# gyro-board.net
KiCad netlist of a schematic drawn in EAGLE
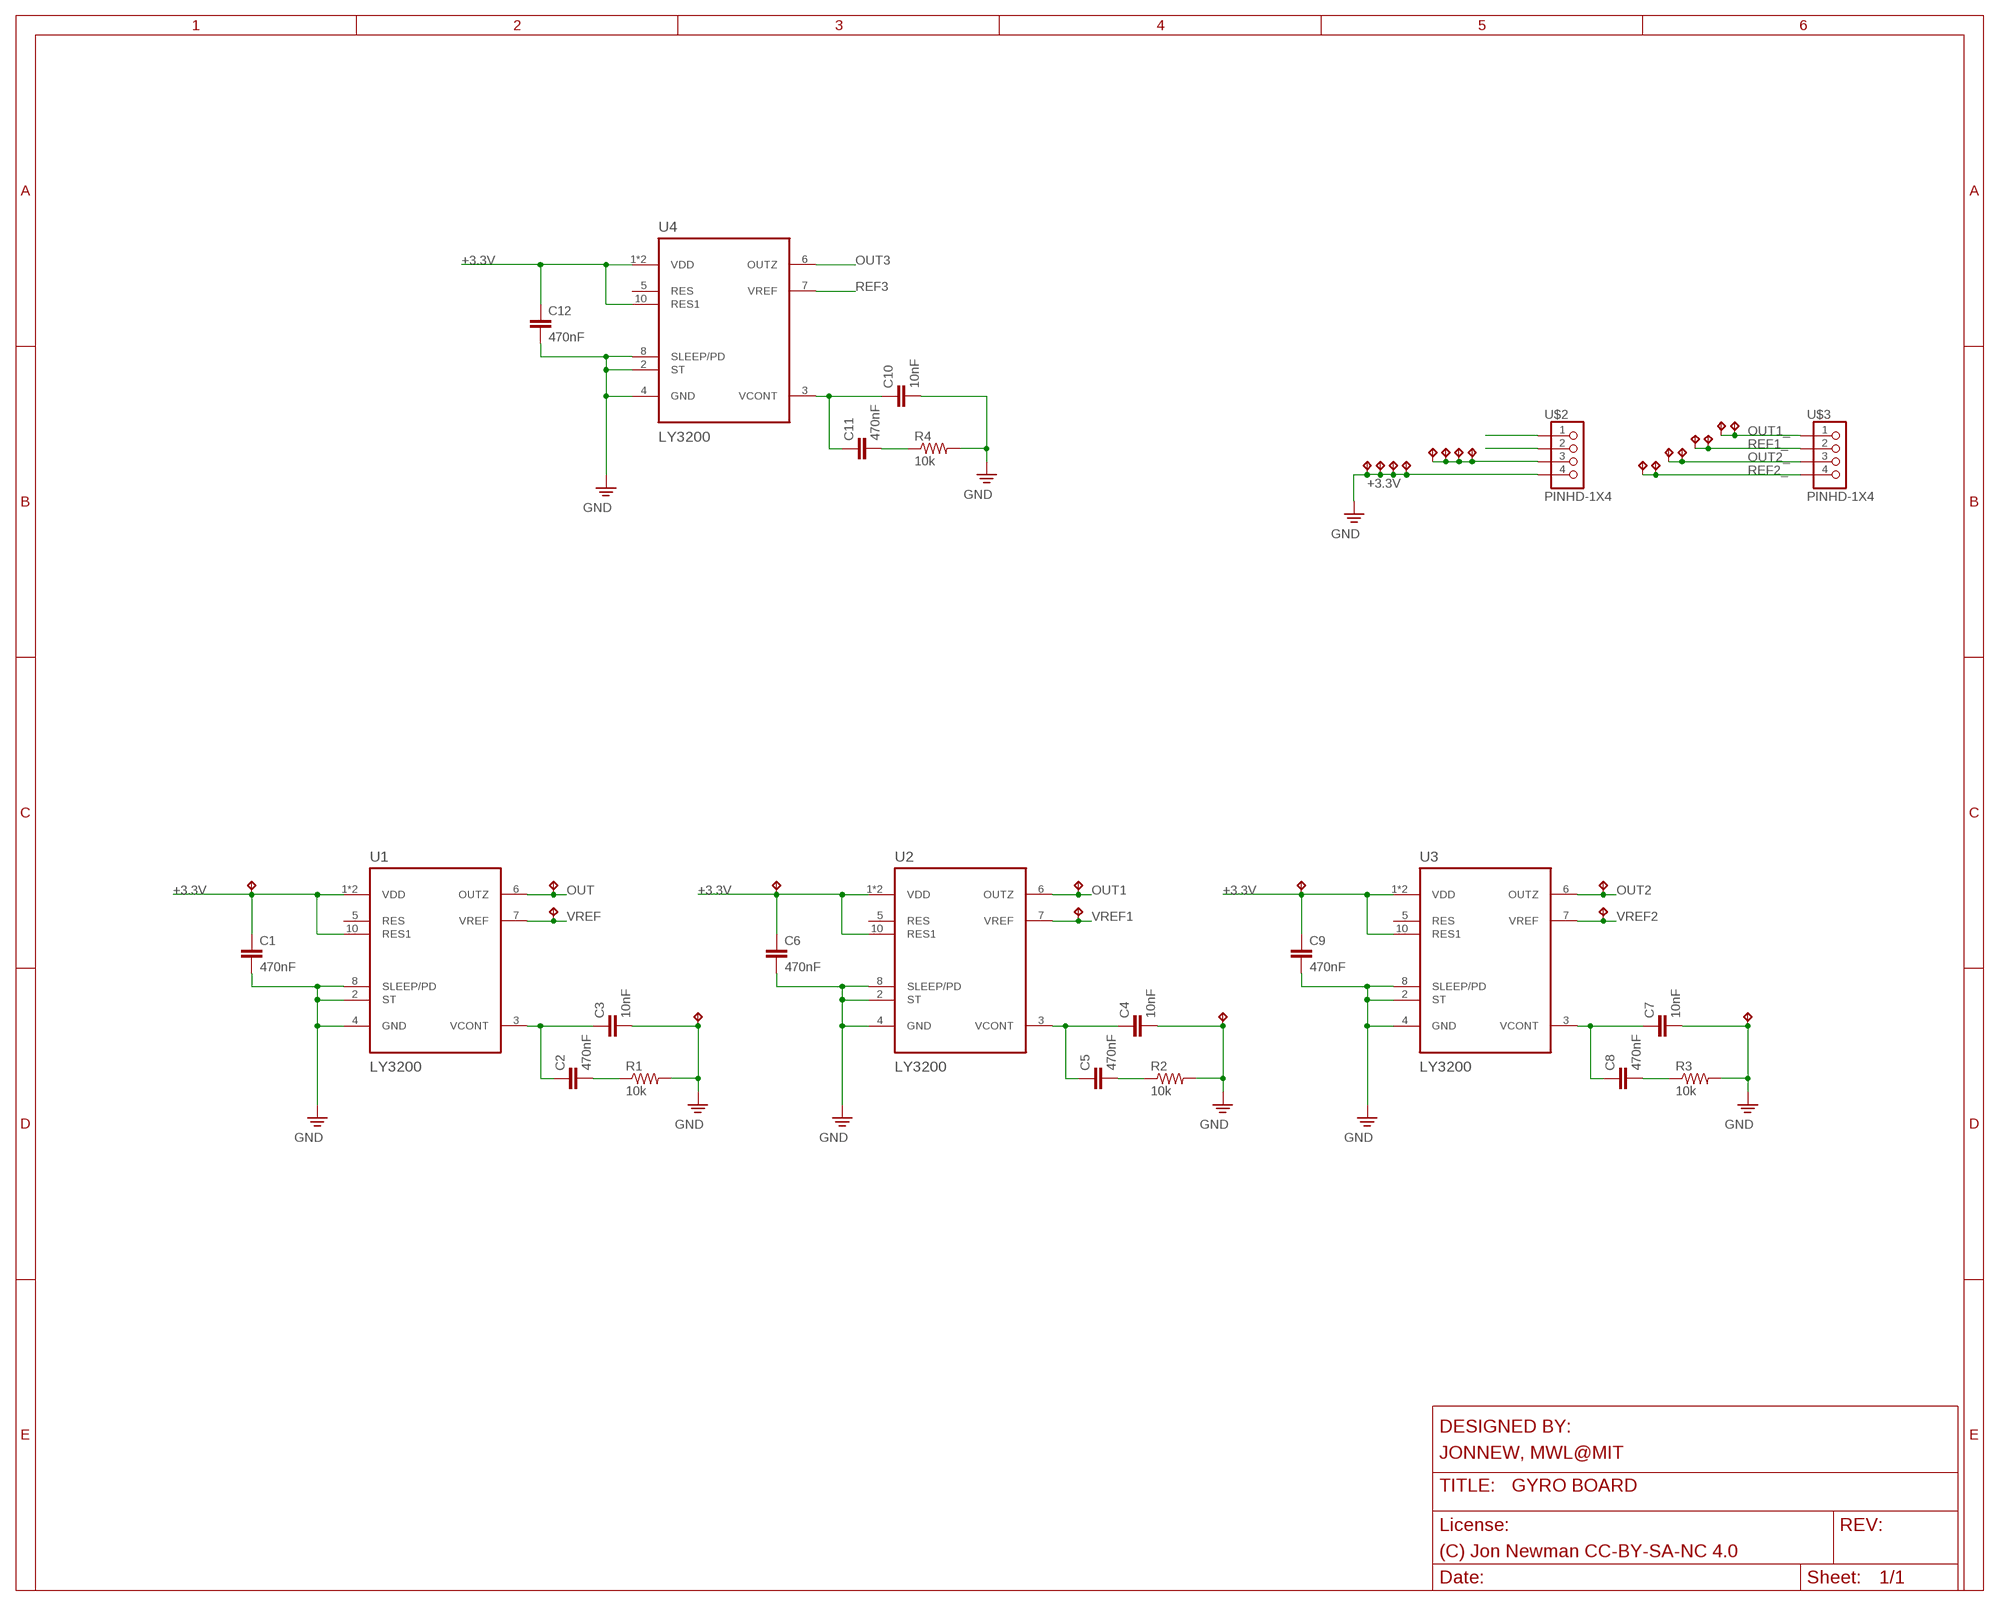
[diagram p0: schematic, sheet 1]

(export (version "E")
  (design (tool "Eeschema 10.0.6"))
  (components
    (comp (ref "C1")
      (value "470nF")
      (footprint "eagle-import:0201")
      (libsource (lib "eagle-import") (part "C_0201"))
    )
    (comp (ref "C2")
      (value "470nF")
      (footprint "eagle-import:0201")
      (libsource (lib "eagle-import") (part "C_0201"))
    )
    (comp (ref "C3")
      (value "10nF")
      (footprint "eagle-import:0201")
      (libsource (lib "eagle-import") (part "C_0201"))
    )
    (comp (ref "C4")
      (value "10nF")
      (footprint "eagle-import:0201")
      (libsource (lib "eagle-import") (part "C_0201"))
    )
    (comp (ref "C5")
      (value "470nF")
      (footprint "eagle-import:0201")
      (libsource (lib "eagle-import") (part "C_0201"))
    )
    (comp (ref "C6")
      (value "470nF")
      (footprint "eagle-import:0201")
      (libsource (lib "eagle-import") (part "C_0201"))
    )
    (comp (ref "C7")
      (value "10nF")
      (footprint "eagle-import:0201")
      (libsource (lib "eagle-import") (part "C_0201"))
    )
    (comp (ref "C8")
      (value "470nF")
      (footprint "eagle-import:0201")
      (libsource (lib "eagle-import") (part "C_0201"))
    )
    (comp (ref "C9")
      (value "470nF")
      (footprint "eagle-import:0201")
      (libsource (lib "eagle-import") (part "C_0201"))
    )
    (comp (ref "C10")
      (value "10nF")
      (footprint "eagle-import:0201")
      (libsource (lib "eagle-import") (part "C_0201"))
    )
    (comp (ref "C11")
      (value "470nF")
      (footprint "eagle-import:0201")
      (libsource (lib "eagle-import") (part "C_0201"))
    )
    (comp (ref "C12")
      (value "470nF")
      (footprint "eagle-import:0201")
      (libsource (lib "eagle-import") (part "C_0201"))
    )
    (comp (ref "R1")
      (value "10k")
      (footprint "eagle-import:0201")
      (libsource (lib "eagle-import") (part "R_0201"))
    )
    (comp (ref "R2")
      (value "10k")
      (footprint "eagle-import:0201")
      (libsource (lib "eagle-import") (part "R_0201"))
    )
    (comp (ref "R3")
      (value "10k")
      (footprint "eagle-import:0201")
      (libsource (lib "eagle-import") (part "R_0201"))
    )
    (comp (ref "R4")
      (value "10k")
      (footprint "eagle-import:0201")
      (libsource (lib "eagle-import") (part "R_0201"))
    )
    (comp (ref "TP1")
      (value "TPTP08SQ")
      (footprint "eagle-import:TP08SQ")
      (libsource (lib "eagle-import") (part "TPTP08SQ"))
    )
    (comp (ref "TP2")
      (value "TPTP08SQ")
      (footprint "eagle-import:TP08SQ")
      (libsource (lib "eagle-import") (part "TPTP08SQ"))
    )
    (comp (ref "TP3")
      (value "TPTP08SQ")
      (footprint "eagle-import:TP08SQ")
      (libsource (lib "eagle-import") (part "TPTP08SQ"))
    )
    (comp (ref "TP4")
      (value "TPTP08SQ")
      (footprint "eagle-import:TP08SQ")
      (libsource (lib "eagle-import") (part "TPTP08SQ"))
    )
    (comp (ref "TP5")
      (value "TPTP08SQ")
      (footprint "eagle-import:TP08SQ")
      (libsource (lib "eagle-import") (part "TPTP08SQ"))
    )
    (comp (ref "TP6")
      (value "TPTP08SQ")
      (footprint "eagle-import:TP08SQ")
      (libsource (lib "eagle-import") (part "TPTP08SQ"))
    )
    (comp (ref "TP7")
      (value "TPTP08SQ")
      (footprint "eagle-import:TP08SQ")
      (libsource (lib "eagle-import") (part "TPTP08SQ"))
    )
    (comp (ref "TP8")
      (value "TPTP08SQ")
      (footprint "eagle-import:TP08SQ")
      (libsource (lib "eagle-import") (part "TPTP08SQ"))
    )
    (comp (ref "TP9")
      (value "TPTP08SQ")
      (footprint "eagle-import:TP08SQ")
      (libsource (lib "eagle-import") (part "TPTP08SQ"))
    )
    (comp (ref "TP10")
      (value "TPTP08SQ")
      (footprint "eagle-import:TP08SQ")
      (libsource (lib "eagle-import") (part "TPTP08SQ"))
    )
    (comp (ref "TP11")
      (value "TPTP08SQ")
      (footprint "eagle-import:TP08SQ")
      (libsource (lib "eagle-import") (part "TPTP08SQ"))
    )
    (comp (ref "TP12")
      (value "TPTP08SQ")
      (footprint "eagle-import:TP08SQ")
      (libsource (lib "eagle-import") (part "TPTP08SQ"))
    )
    (comp (ref "TP13")
      (value "TPTP08SQ")
      (footprint "eagle-import:TP08SQ")
      (libsource (lib "eagle-import") (part "TPTP08SQ"))
    )
    (comp (ref "TP14")
      (value "TPTP08SQ")
      (footprint "eagle-import:TP08SQ")
      (libsource (lib "eagle-import") (part "TPTP08SQ"))
    )
    (comp (ref "TP15")
      (value "TPTP08SQ")
      (footprint "eagle-import:TP08SQ")
      (libsource (lib "eagle-import") (part "TPTP08SQ"))
    )
    (comp (ref "TP16")
      (value "TPTP08SQ")
      (footprint "eagle-import:TP08SQ")
      (libsource (lib "eagle-import") (part "TPTP08SQ"))
    )
    (comp (ref "TP17")
      (value "TPTP08SQ")
      (footprint "eagle-import:TP08SQ")
      (libsource (lib "eagle-import") (part "TPTP08SQ"))
    )
    (comp (ref "TP18")
      (value "TPTP08SQ")
      (footprint "eagle-import:TP08SQ")
      (libsource (lib "eagle-import") (part "TPTP08SQ"))
    )
    (comp (ref "TP19")
      (value "TPTP08SQ")
      (footprint "eagle-import:TP08SQ")
      (libsource (lib "eagle-import") (part "TPTP08SQ"))
    )
    (comp (ref "TP20")
      (value "TPTP08SQ")
      (footprint "eagle-import:TP08SQ")
      (libsource (lib "eagle-import") (part "TPTP08SQ"))
    )
    (comp (ref "TP21")
      (value "TPTP08SQ")
      (footprint "eagle-import:TP08SQ")
      (libsource (lib "eagle-import") (part "TPTP08SQ"))
    )
    (comp (ref "TP22")
      (value "TPTP08SQ")
      (footprint "eagle-import:TP08SQ")
      (libsource (lib "eagle-import") (part "TPTP08SQ"))
    )
    (comp (ref "TP23")
      (value "TPTP08SQ")
      (footprint "eagle-import:TP08SQ")
      (libsource (lib "eagle-import") (part "TPTP08SQ"))
    )
    (comp (ref "TP24")
      (value "TPTP08SQ")
      (footprint "eagle-import:TP08SQ")
      (libsource (lib "eagle-import") (part "TPTP08SQ"))
    )
    (comp (ref "TP25")
      (value "TPTP08SQ")
      (footprint "eagle-import:TP08SQ")
      (libsource (lib "eagle-import") (part "TPTP08SQ"))
    )
    (comp (ref "TP26")
      (value "TPTP08SQ")
      (footprint "eagle-import:TP08SQ")
      (libsource (lib "eagle-import") (part "TPTP08SQ"))
    )
    (comp (ref "TP27")
      (value "TPTP08SQ")
      (footprint "eagle-import:TP08SQ")
      (libsource (lib "eagle-import") (part "TPTP08SQ"))
    )
    (comp (ref "TP28")
      (value "TPTP08SQ")
      (footprint "eagle-import:TP08SQ")
      (libsource (lib "eagle-import") (part "TPTP08SQ"))
    )
    (comp (ref "U$2")
      (value "PINHD-1X4")
      (footprint "eagle-import:1X04")
      (libsource (lib "eagle-import") (part "PINHD-1X4"))
    )
    (comp (ref "U$3")
      (value "PINHD-1X4")
      (footprint "eagle-import:1X04")
      (libsource (lib "eagle-import") (part "PINHD-1X4"))
    )
    (comp (ref "U1")
      (value "LY3200")
      (footprint "eagle-import:LGA-10-COMPACT")
      (libsource (lib "eagle-import") (part "LY3200ALH_LGA-10-COMPACT"))
    )
    (comp (ref "U2")
      (value "LY3200")
      (footprint "eagle-import:LGA-10-COMPACT")
      (libsource (lib "eagle-import") (part "LY3200ALH_LGA-10-COMPACT"))
    )
    (comp (ref "U3")
      (value "LY3200")
      (footprint "eagle-import:LGA-10-COMPACT")
      (libsource (lib "eagle-import") (part "LY3200ALH_LGA-10-COMPACT"))
    )
    (comp (ref "U4")
      (value "LY3200")
      (footprint "eagle-import:LGA-10-COMPACT")
      (libsource (lib "eagle-import") (part "LY3200ALH_LGA-10-COMPACT"))
    )
  )
  (nets
    (net (code "1") (name "/+3.3V") (class "Default")
      (node (ref "C1") (pin "1") (pinfunction "1_1") (pintype "passive"))
      (node (ref "C12") (pin "1") (pinfunction "1_1") (pintype "passive"))
      (node (ref "C6") (pin "1") (pinfunction "1_1") (pintype "passive"))
      (node (ref "C9") (pin "1") (pinfunction "1_1") (pintype "passive"))
      (node (ref "TP1") (pin "TP") (pinfunction "TP_TP") (pintype "input"))
      (node (ref "TP25") (pin "TP") (pinfunction "TP_TP") (pintype "input"))
      (node (ref "TP26") (pin "TP") (pinfunction "TP_TP") (pintype "input"))
      (node (ref "TP27") (pin "TP") (pinfunction "TP_TP") (pintype "input"))
      (node (ref "TP28") (pin "TP") (pinfunction "TP_TP") (pintype "input"))
      (node (ref "TP4") (pin "TP") (pinfunction "TP_TP") (pintype "input"))
      (node (ref "TP9") (pin "TP") (pinfunction "TP_TP") (pintype "input"))
      (node (ref "U$2") (pin "3") (pinfunction "3_3") (pintype "passive"))
      (node (ref "U1") (pin "1") (pinfunction "VDD_1") (pintype "power_in"))
      (node (ref "U1") (pin "10") (pinfunction "RES1_10") (pintype "passive"))
      (node (ref "U1") (pin "9") (pinfunction "VDD_9") (pintype "power_in"))
      (node (ref "U2") (pin "1") (pinfunction "VDD_1") (pintype "power_in"))
      (node (ref "U2") (pin "10") (pinfunction "RES1_10") (pintype "passive"))
      (node (ref "U2") (pin "9") (pinfunction "VDD_9") (pintype "power_in"))
      (node (ref "U3") (pin "1") (pinfunction "VDD_1") (pintype "power_in"))
      (node (ref "U3") (pin "10") (pinfunction "RES1_10") (pintype "passive"))
      (node (ref "U3") (pin "9") (pinfunction "VDD_9") (pintype "power_in"))
      (node (ref "U4") (pin "1") (pinfunction "VDD_1") (pintype "power_in"))
      (node (ref "U4") (pin "10") (pinfunction "RES1_10") (pintype "passive"))
      (node (ref "U4") (pin "9") (pinfunction "VDD_9") (pintype "power_in"))
    )
    (net (code "2") (name "/OUT") (class "Default")
      (node (ref "TP2") (pin "TP") (pinfunction "TP_TP") (pintype "input"))
      (node (ref "U1") (pin "6") (pinfunction "OUTZ_6") (pintype "output"))
    )
    (net (code "3") (name "/OUT1") (class "Default")
      (node (ref "TP6") (pin "TP") (pinfunction "TP_TP") (pintype "input"))
      (node (ref "U2") (pin "6") (pinfunction "OUTZ_6") (pintype "output"))
    )
    (net (code "4") (name "/OUT1_") (class "Default")
      (node (ref "TP20") (pin "TP") (pinfunction "TP_TP") (pintype "input"))
      (node (ref "TP21") (pin "TP") (pinfunction "TP_TP") (pintype "input"))
      (node (ref "U$3") (pin "1") (pinfunction "1_1") (pintype "passive"))
    )
    (net (code "5") (name "/OUT2") (class "Default")
      (node (ref "TP10") (pin "TP") (pinfunction "TP_TP") (pintype "input"))
      (node (ref "U3") (pin "6") (pinfunction "OUTZ_6") (pintype "output"))
    )
    (net (code "6") (name "/OUT2_") (class "Default")
      (node (ref "TP16") (pin "TP") (pinfunction "TP_TP") (pintype "input"))
      (node (ref "TP17") (pin "TP") (pinfunction "TP_TP") (pintype "input"))
      (node (ref "U$3") (pin "3") (pinfunction "3_3") (pintype "passive"))
    )
    (net (code "7") (name "/OUT3") (class "Default")
      (node (ref "U$2") (pin "1") (pinfunction "1_1") (pintype "passive"))
      (node (ref "U4") (pin "6") (pinfunction "OUTZ_6") (pintype "output"))
    )
    (net (code "8") (name "/REF1_") (class "Default")
      (node (ref "TP18") (pin "TP") (pinfunction "TP_TP") (pintype "input"))
      (node (ref "TP19") (pin "TP") (pinfunction "TP_TP") (pintype "input"))
      (node (ref "U$3") (pin "2") (pinfunction "2_2") (pintype "passive"))
    )
    (net (code "9") (name "/REF2_") (class "Default")
      (node (ref "TP14") (pin "TP") (pinfunction "TP_TP") (pintype "input"))
      (node (ref "TP15") (pin "TP") (pinfunction "TP_TP") (pintype "input"))
      (node (ref "U$3") (pin "4") (pinfunction "4_4") (pintype "passive"))
    )
    (net (code "10") (name "/REF3") (class "Default")
      (node (ref "U$2") (pin "2") (pinfunction "2_2") (pintype "passive"))
      (node (ref "U4") (pin "7") (pinfunction "VREF_7") (pintype "output"))
    )
    (net (code "11") (name "/VREF") (class "Default")
      (node (ref "TP5") (pin "TP") (pinfunction "TP_TP") (pintype "input"))
      (node (ref "U1") (pin "7") (pinfunction "VREF_7") (pintype "output"))
    )
    (net (code "12") (name "/VREF1") (class "Default")
      (node (ref "TP8") (pin "TP") (pinfunction "TP_TP") (pintype "input"))
      (node (ref "U2") (pin "7") (pinfunction "VREF_7") (pintype "output"))
    )
    (net (code "13") (name "/VREF2") (class "Default")
      (node (ref "TP12") (pin "TP") (pinfunction "TP_TP") (pintype "input"))
      (node (ref "U3") (pin "7") (pinfunction "VREF_7") (pintype "output"))
    )
    (net (code "14") (name "GND") (class "Default")
      (node (ref "C1") (pin "2") (pinfunction "2_2") (pintype "passive"))
      (node (ref "C10") (pin "2") (pinfunction "2_2") (pintype "passive"))
      (node (ref "C12") (pin "2") (pinfunction "2_2") (pintype "passive"))
      (node (ref "C3") (pin "2") (pinfunction "2_2") (pintype "passive"))
      (node (ref "C4") (pin "2") (pinfunction "2_2") (pintype "passive"))
      (node (ref "C6") (pin "2") (pinfunction "2_2") (pintype "passive"))
      (node (ref "C7") (pin "2") (pinfunction "2_2") (pintype "passive"))
      (node (ref "C9") (pin "2") (pinfunction "2_2") (pintype "passive"))
      (node (ref "R1") (pin "2") (pinfunction "2_2") (pintype "passive"))
      (node (ref "R2") (pin "2") (pinfunction "2_2") (pintype "passive"))
      (node (ref "R3") (pin "2") (pinfunction "2_2") (pintype "passive"))
      (node (ref "R4") (pin "2") (pinfunction "2_2") (pintype "passive"))
      (node (ref "TP11") (pin "TP") (pinfunction "TP_TP") (pintype "input"))
      (node (ref "TP13") (pin "TP") (pinfunction "TP_TP") (pintype "input"))
      (node (ref "TP22") (pin "TP") (pinfunction "TP_TP") (pintype "input"))
      (node (ref "TP23") (pin "TP") (pinfunction "TP_TP") (pintype "input"))
      (node (ref "TP24") (pin "TP") (pinfunction "TP_TP") (pintype "input"))
      (node (ref "TP3") (pin "TP") (pinfunction "TP_TP") (pintype "input"))
      (node (ref "TP7") (pin "TP") (pinfunction "TP_TP") (pintype "input"))
      (node (ref "U$2") (pin "4") (pinfunction "4_4") (pintype "passive"))
      (node (ref "U1") (pin "2") (pinfunction "ST_2") (pintype "bidirectional"))
      (node (ref "U1") (pin "4") (pinfunction "GND_4") (pintype "power_in"))
      (node (ref "U1") (pin "8") (pinfunction "SLEEP/PD_8") (pintype "bidirectional"))
      (node (ref "U2") (pin "2") (pinfunction "ST_2") (pintype "bidirectional"))
      (node (ref "U2") (pin "4") (pinfunction "GND_4") (pintype "power_in"))
      (node (ref "U2") (pin "8") (pinfunction "SLEEP/PD_8") (pintype "bidirectional"))
      (node (ref "U3") (pin "2") (pinfunction "ST_2") (pintype "bidirectional"))
      (node (ref "U3") (pin "4") (pinfunction "GND_4") (pintype "power_in"))
      (node (ref "U3") (pin "8") (pinfunction "SLEEP/PD_8") (pintype "bidirectional"))
      (node (ref "U4") (pin "2") (pinfunction "ST_2") (pintype "bidirectional"))
      (node (ref "U4") (pin "4") (pinfunction "GND_4") (pintype "power_in"))
      (node (ref "U4") (pin "8") (pinfunction "SLEEP/PD_8") (pintype "bidirectional"))
    )
    (net (code "15") (name "Net-(C2-Pad2)") (class "Default")
      (node (ref "C2") (pin "2") (pinfunction "2_2") (pintype "passive"))
      (node (ref "R1") (pin "1") (pinfunction "1_1") (pintype "passive"))
    )
    (net (code "16") (name "Net-(C5-Pad2)") (class "Default")
      (node (ref "C5") (pin "2") (pinfunction "2_2") (pintype "passive"))
      (node (ref "R2") (pin "1") (pinfunction "1_1") (pintype "passive"))
    )
    (net (code "17") (name "Net-(C8-Pad2)") (class "Default")
      (node (ref "C8") (pin "2") (pinfunction "2_2") (pintype "passive"))
      (node (ref "R3") (pin "1") (pinfunction "1_1") (pintype "passive"))
    )
    (net (code "18") (name "Net-(C11-Pad2)") (class "Default")
      (node (ref "C11") (pin "2") (pinfunction "2_2") (pintype "passive"))
      (node (ref "R4") (pin "1") (pinfunction "1_1") (pintype "passive"))
    )
    (net (code "19") (name "Net-(U1-VCONT)") (class "Default")
      (node (ref "C2") (pin "1") (pinfunction "1_1") (pintype "passive"))
      (node (ref "C3") (pin "1") (pinfunction "1_1") (pintype "passive"))
      (node (ref "U1") (pin "3") (pinfunction "VCONT_3") (pintype "passive"))
    )
    (net (code "20") (name "Net-(U2-VCONT)") (class "Default")
      (node (ref "C4") (pin "1") (pinfunction "1_1") (pintype "passive"))
      (node (ref "C5") (pin "1") (pinfunction "1_1") (pintype "passive"))
      (node (ref "U2") (pin "3") (pinfunction "VCONT_3") (pintype "passive"))
    )
    (net (code "21") (name "Net-(U3-VCONT)") (class "Default")
      (node (ref "C7") (pin "1") (pinfunction "1_1") (pintype "passive"))
      (node (ref "C8") (pin "1") (pinfunction "1_1") (pintype "passive"))
      (node (ref "U3") (pin "3") (pinfunction "VCONT_3") (pintype "passive"))
    )
    (net (code "22") (name "Net-(U4-VCONT)") (class "Default")
      (node (ref "C10") (pin "1") (pinfunction "1_1") (pintype "passive"))
      (node (ref "C11") (pin "1") (pinfunction "1_1") (pintype "passive"))
      (node (ref "U4") (pin "3") (pinfunction "VCONT_3") (pintype "passive"))
    )
    (net (code "23") (name "unconnected-(U1-RES-Pad5)") (class "Default")
      (node (ref "U1") (pin "5") (pinfunction "RES_5") (pintype "passive"))
    )
    (net (code "24") (name "unconnected-(U2-RES-Pad5)") (class "Default")
      (node (ref "U2") (pin "5") (pinfunction "RES_5") (pintype "passive"))
    )
    (net (code "25") (name "unconnected-(U3-RES-Pad5)") (class "Default")
      (node (ref "U3") (pin "5") (pinfunction "RES_5") (pintype "passive"))
    )
    (net (code "26") (name "unconnected-(U4-RES-Pad5)") (class "Default")
      (node (ref "U4") (pin "5") (pinfunction "RES_5") (pintype "passive"))
    )
  )
)
